# GRITS_Pi_Hat.net
KiCad netlist of a schematic drawn in Altium Designer
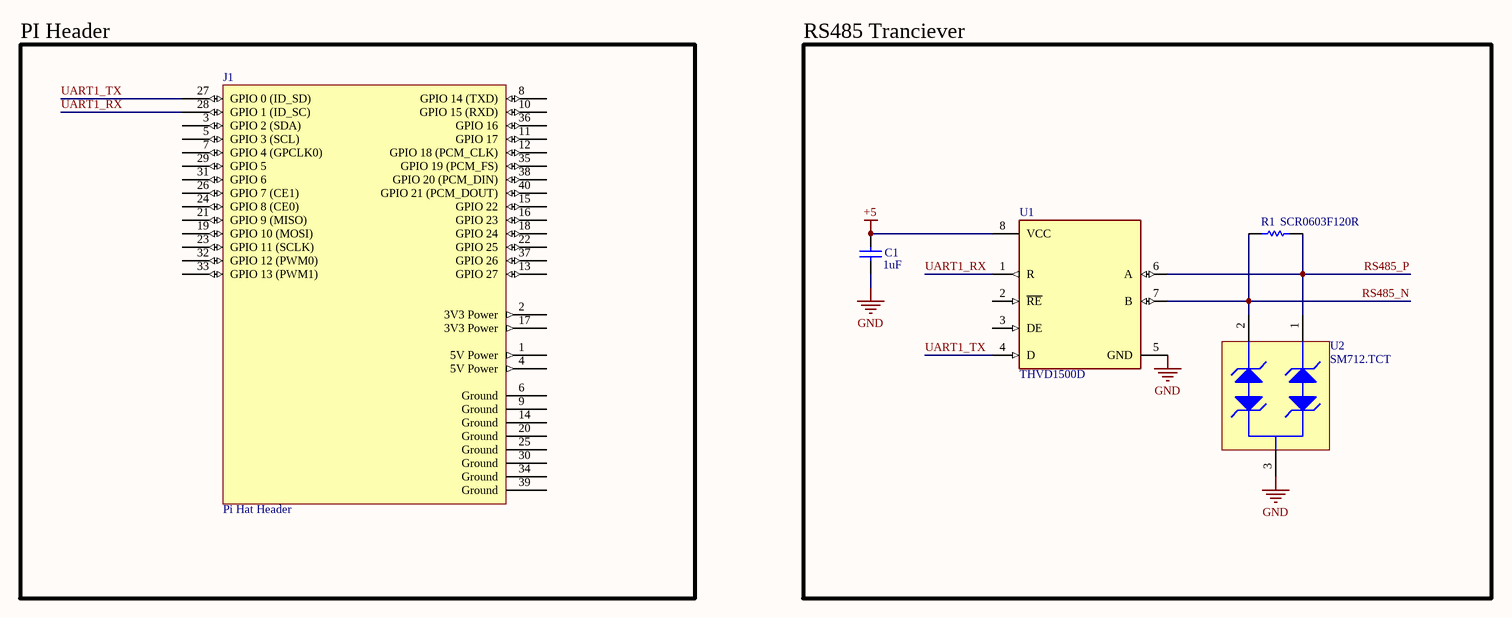
[diagram p0: GRITS Pi Hat.SchDoc]

(export (version "E")
  (design (tool "Eeschema 10.0.6"))
  (components
    (comp (ref "C1")
      (value "1uF")
      (footprint "CL10A105KB8NNNC")
      (description "50V 1uF X5R ±10% 0603 Multilayer Ceramic Capacitors MLCC - SMD/SMT ROHS")
      (fields (field (name "Comment") "CL10A105KB8NNNC"))
      (libsource (lib "GRITS Pi Hat") (part "CL10A105KB8NNNC"))
    )
    (comp (ref "J1")
      (value "Pi Hat Header")
      (footprint "CONN_ESQ-120-33-T-D")
      (description "RaspberryPi 5 Header")
      (libsource (lib "GRITS Pi Hat") (part "Pi Hat Header"))
    )
    (comp (ref "R1")
      (value "SCR0603F120R")
      (footprint "SCR0603F120R")
      (description "50V 1uF X5R ±10% 0603 Multilayer Ceramic Capacitors MLCC - SMD/SMT ROHS")
      (libsource (lib "GRITS Pi Hat") (part "SCR0603F120R"))
    )
    (comp (ref "U1")
      (value "THVD1500D")
      (footprint "FP-D0008B-IPC_A")
      (description "IC TRANSCEIVER HALF 1/1 8SOIC")
      (libsource (lib "Altium Content Vault") (part "2959008ed950a7d942df01a48597072"))
    )
    (comp (ref "U2")
      (value "SM712.TCT")
      (footprint "SMTC-SOT23-3_V")
      (fields (field (name "MANUFACTURER") "Semtech"))
      (libsource (lib "Altium Content Vault") (part "SMTC-SM712.TCT-SOT23-3"))
    )
  )
  (nets
    (net (code "1") (name "+5") (class "Default")
      (node (ref "C1") (pin "1") (pinfunction "1_1") (pintype "passive"))
      (node (ref "U1") (pin "8") (pinfunction "VCC_8") (pintype "power_in"))
    )
    (net (code "2") (name "/RS485_N") (class "Default")
      (node (ref "R1") (pin "1") (pinfunction "1_1") (pintype "passive"))
      (node (ref "U1") (pin "7") (pinfunction "B_7") (pintype "bidirectional"))
      (node (ref "U2") (pin "2") (pinfunction "2_2") (pintype "passive"))
    )
    (net (code "3") (name "/RS485_P") (class "Default")
      (node (ref "R1") (pin "2") (pinfunction "2_2") (pintype "passive"))
      (node (ref "U1") (pin "6") (pinfunction "A_6") (pintype "bidirectional"))
      (node (ref "U2") (pin "1") (pinfunction "1_1") (pintype "passive"))
    )
    (net (code "4") (name "/UART1_RX") (class "Default")
      (node (ref "J1") (pin "28") (pinfunction "GPIO_1_(ID_SC)_28") (pintype "bidirectional"))
      (node (ref "U1") (pin "1") (pinfunction "R_1") (pintype "output"))
    )
    (net (code "5") (name "/UART1_TX") (class "Default")
      (node (ref "J1") (pin "27") (pinfunction "GPIO_0_(ID_SD)_27") (pintype "bidirectional"))
      (node (ref "U1") (pin "4") (pinfunction "D_4") (pintype "input"))
    )
    (net (code "6") (name "GND") (class "Default")
      (node (ref "C1") (pin "2") (pinfunction "2_2") (pintype "passive"))
      (node (ref "U1") (pin "5") (pinfunction "GND_5") (pintype "power_in"))
      (node (ref "U2") (pin "3") (pinfunction "3_3") (pintype "passive"))
    )
    (net (code "7") (name "unconnected-(J1-3V3_Power-Pad2)") (class "Default")
      (node (ref "J1") (pin "2") (pinfunction "3V3_Power_2") (pintype "output"))
    )
    (net (code "8") (name "unconnected-(J1-3V3_Power-Pad17)") (class "Default")
      (node (ref "J1") (pin "17") (pinfunction "3V3_Power_17") (pintype "output"))
    )
    (net (code "9") (name "unconnected-(J1-5V_Power-Pad1)") (class "Default")
      (node (ref "J1") (pin "1") (pinfunction "5V_Power_1") (pintype "output"))
    )
    (net (code "10") (name "unconnected-(J1-5V_Power-Pad4)") (class "Default")
      (node (ref "J1") (pin "4") (pinfunction "5V_Power_4") (pintype "output"))
    )
    (net (code "11") (name "unconnected-(J1-GPIO_2_(SDA)-Pad3)") (class "Default")
      (node (ref "J1") (pin "3") (pinfunction "GPIO_2_(SDA)_3") (pintype "bidirectional"))
    )
    (net (code "12") (name "unconnected-(J1-GPIO_3_(SCL)-Pad5)") (class "Default")
      (node (ref "J1") (pin "5") (pinfunction "GPIO_3_(SCL)_5") (pintype "bidirectional"))
    )
    (net (code "13") (name "unconnected-(J1-GPIO_4_(GPCLK0)-Pad7)") (class "Default")
      (node (ref "J1") (pin "7") (pinfunction "GPIO_4_(GPCLK0)_7") (pintype "bidirectional"))
    )
    (net (code "14") (name "unconnected-(J1-GPIO_5-Pad29)") (class "Default")
      (node (ref "J1") (pin "29") (pinfunction "GPIO_5_29") (pintype "bidirectional"))
    )
    (net (code "15") (name "unconnected-(J1-GPIO_6-Pad31)") (class "Default")
      (node (ref "J1") (pin "31") (pinfunction "GPIO_6_31") (pintype "bidirectional"))
    )
    (net (code "16") (name "unconnected-(J1-GPIO_7_(CE1)-Pad26)") (class "Default")
      (node (ref "J1") (pin "26") (pinfunction "GPIO_7_(CE1)_26") (pintype "bidirectional"))
    )
    (net (code "17") (name "unconnected-(J1-GPIO_8_(CE0)-Pad24)") (class "Default")
      (node (ref "J1") (pin "24") (pinfunction "GPIO_8_(CE0)_24") (pintype "bidirectional"))
    )
    (net (code "18") (name "unconnected-(J1-GPIO_9_(MISO)-Pad21)") (class "Default")
      (node (ref "J1") (pin "21") (pinfunction "GPIO_9_(MISO)_21") (pintype "bidirectional"))
    )
    (net (code "19") (name "unconnected-(J1-GPIO_10_(MOSI)-Pad19)") (class "Default")
      (node (ref "J1") (pin "19") (pinfunction "GPIO_10_(MOSI)_19") (pintype "bidirectional"))
    )
    (net (code "20") (name "unconnected-(J1-GPIO_11_(SCLK)-Pad23)") (class "Default")
      (node (ref "J1") (pin "23") (pinfunction "GPIO_11_(SCLK)_23") (pintype "bidirectional"))
    )
    (net (code "21") (name "unconnected-(J1-GPIO_12_(PWM0)-Pad32)") (class "Default")
      (node (ref "J1") (pin "32") (pinfunction "GPIO_12_(PWM0)_32") (pintype "bidirectional"))
    )
    (net (code "22") (name "unconnected-(J1-GPIO_13_(PWM1)-Pad33)") (class "Default")
      (node (ref "J1") (pin "33") (pinfunction "GPIO_13_(PWM1)_33") (pintype "bidirectional"))
    )
    (net (code "23") (name "unconnected-(J1-GPIO_14_(TXD)-Pad8)") (class "Default")
      (node (ref "J1") (pin "8") (pinfunction "GPIO_14_(TXD)_8") (pintype "bidirectional"))
    )
    (net (code "24") (name "unconnected-(J1-GPIO_15_(RXD)-Pad10)") (class "Default")
      (node (ref "J1") (pin "10") (pinfunction "GPIO_15_(RXD)_10") (pintype "bidirectional"))
    )
    (net (code "25") (name "unconnected-(J1-GPIO_16-Pad36)") (class "Default")
      (node (ref "J1") (pin "36") (pinfunction "GPIO_16_36") (pintype "bidirectional"))
    )
    (net (code "26") (name "unconnected-(J1-GPIO_17-Pad11)") (class "Default")
      (node (ref "J1") (pin "11") (pinfunction "GPIO_17_11") (pintype "bidirectional"))
    )
    (net (code "27") (name "unconnected-(J1-GPIO_18_(PCM_CLK)-Pad12)") (class "Default")
      (node (ref "J1") (pin "12") (pinfunction "GPIO_18_(PCM_CLK)_12") (pintype "bidirectional"))
    )
    (net (code "28") (name "unconnected-(J1-GPIO_19_(PCM_FS)-Pad35)") (class "Default")
      (node (ref "J1") (pin "35") (pinfunction "GPIO_19_(PCM_FS)_35") (pintype "bidirectional"))
    )
    (net (code "29") (name "unconnected-(J1-GPIO_20_(PCM_DIN)-Pad38)") (class "Default")
      (node (ref "J1") (pin "38") (pinfunction "GPIO_20_(PCM_DIN)_38") (pintype "bidirectional"))
    )
    (net (code "30") (name "unconnected-(J1-GPIO_21_(PCM_DOUT)-Pad40)") (class "Default")
      (node (ref "J1") (pin "40") (pinfunction "GPIO_21_(PCM_DOUT)_40") (pintype "bidirectional"))
    )
    (net (code "31") (name "unconnected-(J1-GPIO_22-Pad15)") (class "Default")
      (node (ref "J1") (pin "15") (pinfunction "GPIO_22_15") (pintype "bidirectional"))
    )
    (net (code "32") (name "unconnected-(J1-GPIO_23-Pad16)") (class "Default")
      (node (ref "J1") (pin "16") (pinfunction "GPIO_23_16") (pintype "bidirectional"))
    )
    (net (code "33") (name "unconnected-(J1-GPIO_24-Pad18)") (class "Default")
      (node (ref "J1") (pin "18") (pinfunction "GPIO_24_18") (pintype "bidirectional"))
    )
    (net (code "34") (name "unconnected-(J1-GPIO_25-Pad22)") (class "Default")
      (node (ref "J1") (pin "22") (pinfunction "GPIO_25_22") (pintype "bidirectional"))
    )
    (net (code "35") (name "unconnected-(J1-GPIO_26-Pad37)") (class "Default")
      (node (ref "J1") (pin "37") (pinfunction "GPIO_26_37") (pintype "bidirectional"))
    )
    (net (code "36") (name "unconnected-(J1-GPIO_27-Pad13)") (class "Default")
      (node (ref "J1") (pin "13") (pinfunction "GPIO_27_13") (pintype "bidirectional"))
    )
    (net (code "37") (name "unconnected-(J1-Ground-Pad6)") (class "Default")
      (node (ref "J1") (pin "6") (pinfunction "Ground_6") (pintype "power_in"))
    )
    (net (code "38") (name "unconnected-(J1-Ground-Pad9)") (class "Default")
      (node (ref "J1") (pin "9") (pinfunction "Ground_9") (pintype "power_in"))
    )
    (net (code "39") (name "unconnected-(J1-Ground-Pad14)") (class "Default")
      (node (ref "J1") (pin "14") (pinfunction "Ground_14") (pintype "power_in"))
    )
    (net (code "40") (name "unconnected-(J1-Ground-Pad20)") (class "Default")
      (node (ref "J1") (pin "20") (pinfunction "Ground_20") (pintype "power_in"))
    )
    (net (code "41") (name "unconnected-(J1-Ground-Pad25)") (class "Default")
      (node (ref "J1") (pin "25") (pinfunction "Ground_25") (pintype "power_in"))
    )
    (net (code "42") (name "unconnected-(J1-Ground-Pad30)") (class "Default")
      (node (ref "J1") (pin "30") (pinfunction "Ground_30") (pintype "power_in"))
    )
    (net (code "43") (name "unconnected-(J1-Ground-Pad34)") (class "Default")
      (node (ref "J1") (pin "34") (pinfunction "Ground_34") (pintype "power_in"))
    )
    (net (code "44") (name "unconnected-(J1-Ground-Pad39)") (class "Default")
      (node (ref "J1") (pin "39") (pinfunction "Ground_39") (pintype "power_in"))
    )
    (net (code "45") (name "unconnected-(U1-DE-Pad3)") (class "Default")
      (node (ref "U1") (pin "3") (pinfunction "DE_3") (pintype "input"))
    )
    (net (code "46") (name "unconnected-(U1-~{RE}-Pad2)") (class "Default")
      (node (ref "U1") (pin "2") (pinfunction "~{RE}_2") (pintype "input"))
    )
  )
)
